# Manchester-Comparator_Module.net
KiCad netlist of a schematic drawn in Altium Designer
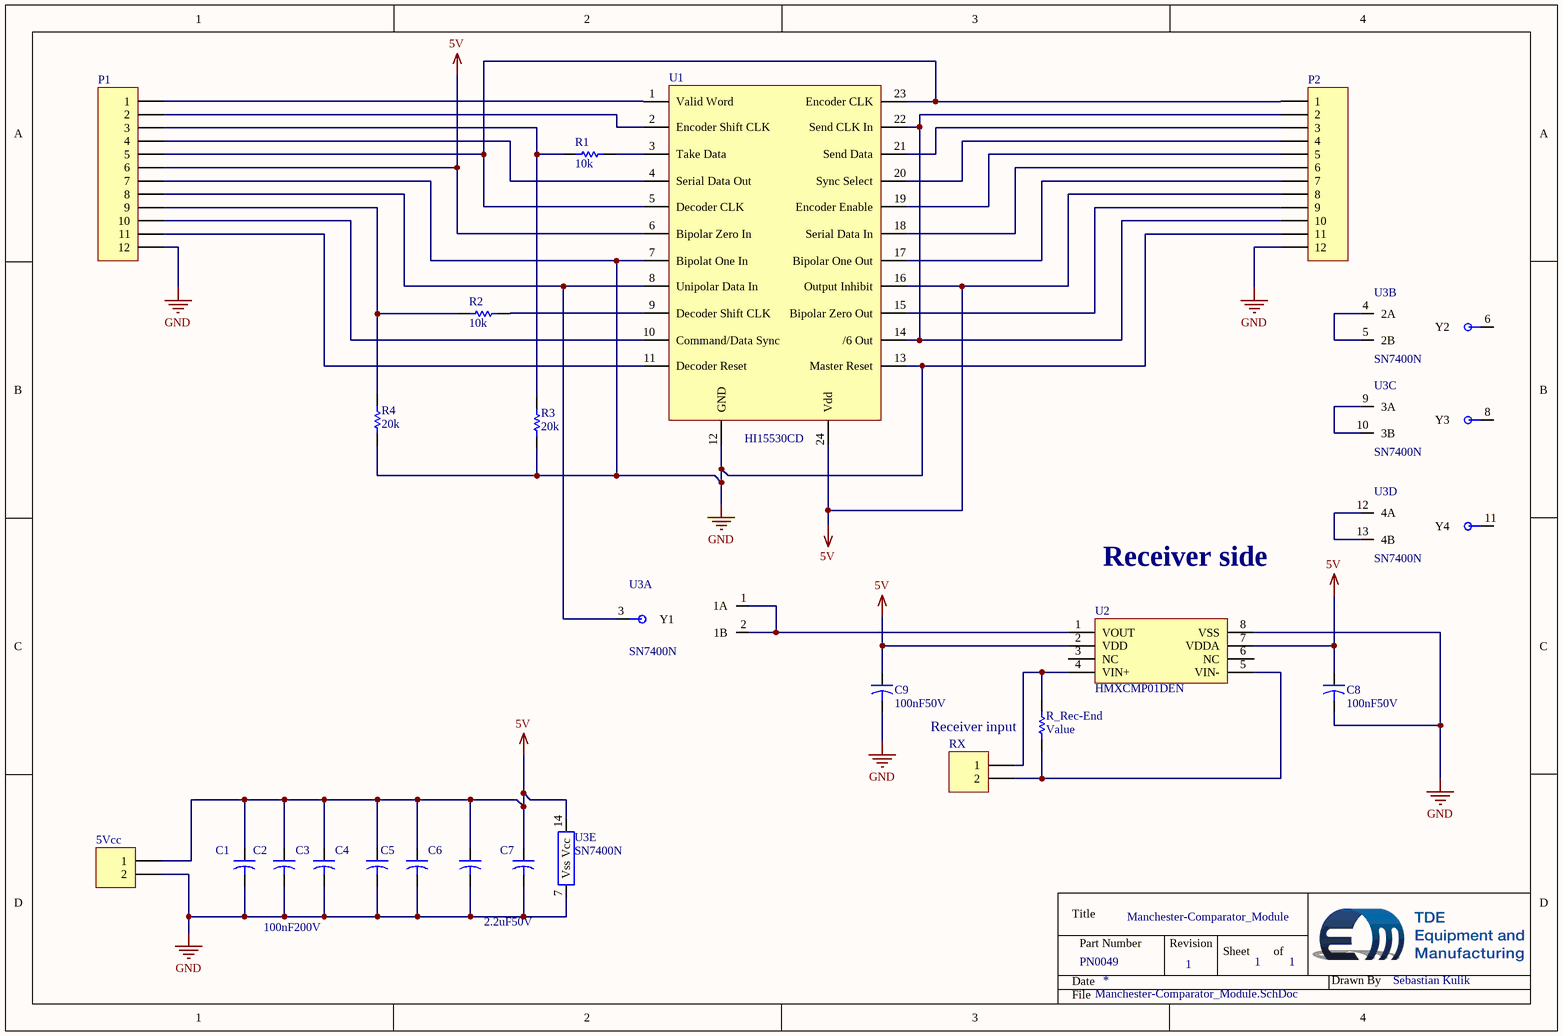
[diagram p0: Manchester-Comparator_Module.SchDoc]

(export (version "E")
  (design (tool "Eeschema 10.0.6"))
  (components
    (comp (ref "*") (value "Eye") (footprint "Eye") (libsource (lib "ICs") (part "Eye")))
    (comp (ref "**") (value "Eye") (footprint "Eye") (libsource (lib "ICs") (part "Eye")))
    (comp (ref "5Vcc")
      (value "PHOENIX_1715721")
      (footprint "Phoenix-2-5_08")
      (description "Phoenix, 2 pol, 5.08mm, 22A, 715721")
      (fields (field (name "MANUFACTURER") "Phoenix") (field (name "PUBLISHER") "Sebastian Kulik"))
      (libsource (lib "Connectors") (part "2Pol_1715721"))
    )
    (comp (ref "C1")
      (value "Capacitor-Dummy-THT")
      (footprint "Dummy-10mm")
      (fields (field (name "PUBLISHER") "Sebastian Kulik"))
      (libsource (lib "Capacitors") (part "Capacitor-Dummy-THT"))
    )
    (comp (ref "C2")
      (value "Capacitor-Dummy-THT")
      (footprint "Dummy-10mm")
      (fields (field (name "PUBLISHER") "Sebastian Kulik"))
      (libsource (lib "Capacitors") (part "Capacitor-Dummy-THT"))
    )
    (comp (ref "C3")
      (value "100nF200V")
      (footprint "Dummy-10mm")
      (description "Capacitor-Dummy-THT")
      (fields (field (name "PUBLISHER") "Sebastian Kulik"))
      (libsource (lib "Capacitors") (part "Capacitor-Dummy-THT"))
    )
    (comp (ref "C4")
      (value "Capacitor-Dummy-THT")
      (footprint "Dummy-10mm")
      (fields (field (name "PUBLISHER") "Sebastian Kulik"))
      (libsource (lib "Capacitors") (part "Capacitor-Dummy-THT"))
    )
    (comp (ref "C5")
      (value "Capacitor-Dummy-THT")
      (footprint "Dummy-10mm")
      (fields (field (name "PUBLISHER") "Sebastian Kulik"))
      (libsource (lib "Capacitors") (part "Capacitor-Dummy-THT"))
    )
    (comp (ref "C6")
      (value "Capacitor-Dummy-THT")
      (footprint "Dummy-10mm")
      (fields (field (name "PUBLISHER") "Sebastian Kulik"))
      (libsource (lib "Capacitors") (part "Capacitor-Dummy-THT"))
    )
    (comp (ref "C7")
      (value "2.2uF50V")
      (footprint "Dummy-10mm")
      (description "Capacitor-Dummy-THT")
      (fields (field (name "PUBLISHER") "Sebastian Kulik"))
      (libsource (lib "Capacitors") (part "Capacitor-Dummy-THT"))
    )
    (comp (ref "C8")
      (value "100nF50V")
      (footprint "KEMET-C052H")
      (description "High Temp C series, NP0, 10%, 50V")
      (fields
        (field (name "MANUFACTURER") "Kemet")
        (field (name "Comment") "100nF_50V_THT_HT")
        (field (name "PUBLISHER") "Sebastian Kulik")
      )
      (libsource (lib "Capacitors") (part "100nF_50V_THT_HT"))
    )
    (comp (ref "C9")
      (value "100nF50V")
      (footprint "KEMET-C052H")
      (description "High Temp C series, NP0, 10%, 50V")
      (fields
        (field (name "MANUFACTURER") "Kemet")
        (field (name "Comment") "100nF_50V_THT_HT")
        (field (name "PUBLISHER") "Sebastian Kulik")
      )
      (libsource (lib "Capacitors") (part "100nF_50V_THT_HT"))
    )
    (comp (ref "P1")
      (value "Plug_12_2.54")
      (footprint "HDR1X12_2.54")
      (description "Plug, 11-Pin")
      (fields (field (name "MANUFACTURER") "WE") (field (name "PUBLISHER") "Sebastian Kulik"))
      (libsource (lib "") (part "Plug_12_2.54_1"))
    )
    (comp (ref "P2")
      (value "Plug_12_2.54")
      (footprint "HDR1X12_2.54")
      (description "Plug, 11-Pin")
      (fields (field (name "MANUFACTURER") "WE") (field (name "PUBLISHER") "Sebastian Kulik"))
      (libsource (lib "Connectors") (part "Plug_12_2.54"))
    )
    (comp (ref "R1")
      (value "10k")
      (footprint "Dummy-10mm")
      (description "RN60 Series, 1%, 175°C")
      (fields
        (field (name "MANUFACTURER") "Vishay")
        (field (name "Comment") "10k_10mm-HT")
        (field (name "PUBLISHER") "Sebastian Kulik")
      )
      (libsource (lib "Resistors") (part "10k_10mm-HT"))
    )
    (comp (ref "R2")
      (value "10k")
      (footprint "Dummy-10mm")
      (description "RN60 Series, 1%, 175°C")
      (fields
        (field (name "MANUFACTURER") "Vishay")
        (field (name "Comment") "10k_10mm-HT")
        (field (name "PUBLISHER") "Sebastian Kulik")
      )
      (libsource (lib "Resistors") (part "10k_10mm-HT"))
    )
    (comp (ref "R3")
      (value "20k")
      (footprint "Dummy-10mm")
      (description "RN60 Series, 1%, 175°C")
      (fields
        (field (name "MANUFACTURER") "Vishay")
        (field (name "Comment") "20k_10mm-HT")
        (field (name "PUBLISHER") "Sebastian Kulik")
      )
      (libsource (lib "Resistors") (part "20k_10mm-HT"))
    )
    (comp (ref "R4")
      (value "20k")
      (footprint "Dummy-10mm")
      (description "RN60 Series, 1%, 175°C")
      (fields
        (field (name "MANUFACTURER") "Vishay")
        (field (name "Comment") "20k_10mm-HT")
        (field (name "PUBLISHER") "Sebastian Kulik")
      )
      (libsource (lib "Resistors") (part "20k_10mm-HT"))
    )
    (comp (ref "RX")
      (value "PHOENIX_1715721")
      (footprint "Phoenix-2-5_08")
      (description "Phoenix, 2 pol, 5.08mm, 22A, 715721")
      (fields (field (name "MANUFACTURER") "Phoenix") (field (name "PUBLISHER") "Sebastian Kulik"))
      (libsource (lib "Connectors") (part "2Pol_1715721"))
    )
    (comp (ref "R_Rec-End")
      (value "Value")
      (footprint "Dummy-10mm")
      (description "Resistor-Dummy-THT")
      (fields (field (name "PUBLISHER") "Sebastian Kulik"))
      (libsource (lib "Resistors") (part "Resistor-Dummy-THT"))
    )
    (comp (ref "U1")
      (value "HI15530CD")
      (footprint "DIP-24-Ceramic-HT")
      (description "Manchester Encoder / Decoder")
      (fields (field (name "MANUFACTURER") "HolTEc") (field (name "PUBLISHER") "Sebastian Kulik"))
      (libsource (lib "ICs") (part "HI15530CD"))
    )
    (comp (ref "U2")
      (value "HMXCMP01DEN")
      (footprint "Honeywell-SO8")
      (description "HiTemp Comparator")
      (fields (field (name "MANUFACTURER") "X-Rel") (field (name "PUBLISHER") "Sebastian Kulik"))
      (libsource (lib "ICs") (part "HMXCMP01DEN"))
    )
    (comp (ref "U3")
      (value "SN7400N")
      (footprint "DIP-14")
      (description "Quad NAND, TTL")
      (fields (field (name "MANUFACTURER") "TI") (field (name "PUBLISHER") "Sebastian Kulik"))
      (libsource (lib "") (part "SN7400N_1"))
    )
  )
  (nets
    (net (code "1") (name "5V") (class "Default")
      (node (ref "5Vcc") (pin "1") (pinfunction "1_1") (pintype "passive"))
      (node (ref "C1") (pin "1") (pinfunction "1_1") (pintype "passive"))
      (node (ref "C2") (pin "1") (pinfunction "1_1") (pintype "passive"))
      (node (ref "C3") (pin "1") (pinfunction "1_1") (pintype "passive"))
      (node (ref "C4") (pin "1") (pinfunction "1_1") (pintype "passive"))
      (node (ref "C5") (pin "1") (pinfunction "1_1") (pintype "passive"))
      (node (ref "C6") (pin "1") (pinfunction "1_1") (pintype "passive"))
      (node (ref "C7") (pin "1") (pinfunction "1_1") (pintype "passive"))
      (node (ref "C8") (pin "1") (pinfunction "1_1") (pintype "passive"))
      (node (ref "C9") (pin "1") (pinfunction "1_1") (pintype "passive"))
      (node (ref "P1") (pin "6") (pinfunction "6_6") (pintype "passive"))
      (node (ref "P2") (pin "8") (pinfunction "8_8") (pintype "passive"))
      (node (ref "U1") (pin "16") (pinfunction "Output_Inhibit_16") (pintype "passive"))
      (node (ref "U1") (pin "24") (pinfunction "Vdd_24") (pintype "passive"))
      (node (ref "U1") (pin "6") (pinfunction "Bipolar_Zero_In_6") (pintype "passive"))
      (node (ref "U2") (pin "2") (pinfunction "VDD_2") (pintype "passive"))
      (node (ref "U2") (pin "7") (pinfunction "VDDA_7") (pintype "passive"))
      (node (ref "U3") (pin "14") (pinfunction "Vcc_14") (pintype "passive"))
    )
    (net (code "2") (name "GND") (class "Default")
      (node (ref "5Vcc") (pin "2") (pinfunction "2_2") (pintype "passive"))
      (node (ref "C1") (pin "2") (pinfunction "2_2") (pintype "passive"))
      (node (ref "C2") (pin "2") (pinfunction "2_2") (pintype "passive"))
      (node (ref "C3") (pin "2") (pinfunction "2_2") (pintype "passive"))
      (node (ref "C4") (pin "2") (pinfunction "2_2") (pintype "passive"))
      (node (ref "C5") (pin "2") (pinfunction "2_2") (pintype "passive"))
      (node (ref "C6") (pin "2") (pinfunction "2_2") (pintype "passive"))
      (node (ref "C7") (pin "2") (pinfunction "2_2") (pintype "passive"))
      (node (ref "C8") (pin "2") (pinfunction "2_2") (pintype "passive"))
      (node (ref "C9") (pin "2") (pinfunction "2_2") (pintype "passive"))
      (node (ref "P1") (pin "12") (pinfunction "12_12") (pintype "passive"))
      (node (ref "P1") (pin "7") (pinfunction "7_7") (pintype "passive"))
      (node (ref "P2") (pin "11") (pinfunction "11_11") (pintype "passive"))
      (node (ref "P2") (pin "12") (pinfunction "12_12") (pintype "passive"))
      (node (ref "R3") (pin "1") (pinfunction "1_1") (pintype "passive"))
      (node (ref "R4") (pin "1") (pinfunction "1_1") (pintype "passive"))
      (node (ref "U1") (pin "12") (pinfunction "GND_12") (pintype "power_in"))
      (node (ref "U1") (pin "13") (pinfunction "Master_Reset_13") (pintype "passive"))
      (node (ref "U1") (pin "7") (pinfunction "Bipolat_One_In_7") (pintype "passive"))
      (node (ref "U2") (pin "8") (pinfunction "VSS_8") (pintype "passive"))
      (node (ref "U3") (pin "7") (pinfunction "Vss_7") (pintype "passive"))
    )
    (net (code "3") (name "Net-(P1-Pad3)") (class "Default")
      (node (ref "P1") (pin "3") (pinfunction "3_3") (pintype "passive"))
      (node (ref "R1") (pin "2") (pinfunction "2_2") (pintype "passive"))
      (node (ref "R3") (pin "2") (pinfunction "2_2") (pintype "passive"))
    )
    (net (code "4") (name "Net-(P1-Pad9)") (class "Default")
      (node (ref "P1") (pin "9") (pinfunction "9_9") (pintype "passive"))
      (node (ref "R2") (pin "2") (pinfunction "2_2") (pintype "passive"))
      (node (ref "R4") (pin "2") (pinfunction "2_2") (pintype "passive"))
    )
    (net (code "5") (name "Net-(U1-Bipolar_One_Out)") (class "Default")
      (node (ref "P2") (pin "7") (pinfunction "7_7") (pintype "passive"))
      (node (ref "U1") (pin "17") (pinfunction "Bipolar_One_Out_17") (pintype "passive"))
    )
    (net (code "6") (name "Net-(U1-Bipolar_Zero_Out)") (class "Default")
      (node (ref "P2") (pin "9") (pinfunction "9_9") (pintype "passive"))
      (node (ref "U1") (pin "15") (pinfunction "Bipolar_Zero_Out_15") (pintype "power_in"))
    )
    (net (code "7") (name "Net-(U1-Command{slash}Data_Sync)") (class "Default")
      (node (ref "P1") (pin "10") (pinfunction "10_10") (pintype "passive"))
      (node (ref "U1") (pin "10") (pinfunction "Command/Data_Sync_10") (pintype "power_in"))
    )
    (net (code "8") (name "Net-(U1-Decoder_CLK)") (class "Default")
      (node (ref "P1") (pin "5") (pinfunction "5_5") (pintype "passive"))
      (node (ref "P2") (pin "1") (pinfunction "1_1") (pintype "passive"))
      (node (ref "U1") (pin "23") (pinfunction "Encoder_CLK_23") (pintype "passive"))
      (node (ref "U1") (pin "5") (pinfunction "Decoder_CLK_5") (pintype "passive"))
    )
    (net (code "9") (name "Net-(U1-Decoder_Reset)") (class "Default")
      (node (ref "P1") (pin "11") (pinfunction "11_11") (pintype "passive"))
      (node (ref "U1") (pin "11") (pinfunction "Decoder_Reset_11") (pintype "power_in"))
    )
    (net (code "10") (name "Net-(U1-Decoder_Shift_CLK)") (class "Default")
      (node (ref "R2") (pin "1") (pinfunction "1_1") (pintype "passive"))
      (node (ref "U1") (pin "9") (pinfunction "Decoder_Shift_CLK_9") (pintype "power_in"))
    )
    (net (code "11") (name "Net-(U1-Encoder_Enable)") (class "Default")
      (node (ref "P2") (pin "5") (pinfunction "5_5") (pintype "passive"))
      (node (ref "U1") (pin "19") (pinfunction "Encoder_Enable_19") (pintype "passive"))
    )
    (net (code "12") (name "Net-(U1-Encoder_Shift_CLK)") (class "Default")
      (node (ref "P1") (pin "2") (pinfunction "2_2") (pintype "passive"))
      (node (ref "U1") (pin "2") (pinfunction "Encoder_Shift_CLK_2") (pintype "passive"))
    )
    (net (code "13") (name "Net-(U1-Send_CLK_In)") (class "Default")
      (node (ref "P2") (pin "10") (pinfunction "10_10") (pintype "passive"))
      (node (ref "P2") (pin "2") (pinfunction "2_2") (pintype "passive"))
      (node (ref "U1") (pin "14") (pinfunction "/6_Out_14") (pintype "passive"))
      (node (ref "U1") (pin "22") (pinfunction "Send_CLK_In_22") (pintype "passive"))
    )
    (net (code "14") (name "Net-(U1-Send_Data)") (class "Default")
      (node (ref "P2") (pin "3") (pinfunction "3_3") (pintype "passive"))
      (node (ref "U1") (pin "21") (pinfunction "Send_Data_21") (pintype "passive"))
    )
    (net (code "15") (name "Net-(U1-Serial_Data_In)") (class "Default")
      (node (ref "P2") (pin "6") (pinfunction "6_6") (pintype "passive"))
      (node (ref "U1") (pin "18") (pinfunction "Serial_Data_In_18") (pintype "passive"))
    )
    (net (code "16") (name "Net-(U1-Serial_Data_Out)") (class "Default")
      (node (ref "P1") (pin "4") (pinfunction "4_4") (pintype "passive"))
      (node (ref "U1") (pin "4") (pinfunction "Serial_Data_Out_4") (pintype "passive"))
    )
    (net (code "17") (name "Net-(U1-Sync_Select)") (class "Default")
      (node (ref "P2") (pin "4") (pinfunction "4_4") (pintype "passive"))
      (node (ref "U1") (pin "20") (pinfunction "Sync_Select_20") (pintype "passive"))
    )
    (net (code "18") (name "Net-(U1-Take_Data)") (class "Default")
      (node (ref "R1") (pin "1") (pinfunction "1_1") (pintype "passive"))
      (node (ref "U1") (pin "3") (pinfunction "Take_Data_3") (pintype "passive"))
    )
    (net (code "19") (name "Net-(U1-Unipolar_Data_In)") (class "Default")
      (node (ref "P1") (pin "8") (pinfunction "8_8") (pintype "passive"))
      (node (ref "U1") (pin "8") (pinfunction "Unipolar_Data_In_8") (pintype "power_in"))
      (node (ref "U3") (pin "3") (pinfunction "Y1_3") (pintype "passive"))
    )
    (net (code "20") (name "Net-(U1-Valid_Word)") (class "Default")
      (node (ref "P1") (pin "1") (pinfunction "1_1") (pintype "passive"))
      (node (ref "U1") (pin "1") (pinfunction "Valid_Word_1") (pintype "passive"))
    )
    (net (code "21") (name "Net-(U2-VIN+)") (class "Default")
      (node (ref "RX") (pin "1") (pinfunction "1_1") (pintype "passive"))
      (node (ref "R_Rec-End") (pin "2") (pinfunction "2_2") (pintype "passive"))
      (node (ref "U2") (pin "4") (pinfunction "VIN+_4") (pintype "passive"))
    )
    (net (code "22") (name "Net-(U2-VIN-)") (class "Default")
      (node (ref "RX") (pin "2") (pinfunction "2_2") (pintype "passive"))
      (node (ref "R_Rec-End") (pin "1") (pinfunction "1_1") (pintype "passive"))
      (node (ref "U2") (pin "5") (pinfunction "VIN-_5") (pintype "passive"))
    )
    (net (code "23") (name "Net-(U2-VOUT)") (class "Default")
      (node (ref "U2") (pin "1") (pinfunction "VOUT_1") (pintype "passive"))
      (node (ref "U3") (pin "1") (pinfunction "1A_1") (pintype "passive"))
      (node (ref "U3") (pin "2") (pinfunction "1B_2") (pintype "passive"))
    )
    (net (code "24") (name "Net-(U3B-2A)") (class "Default")
      (node (ref "U3") (pin "4") (pinfunction "2A_4") (pintype "passive"))
      (node (ref "U3") (pin "5") (pinfunction "2B_5") (pintype "passive"))
    )
    (net (code "25") (name "Net-(U3C-3A)") (class "Default")
      (node (ref "U3") (pin "10") (pinfunction "3B_10") (pintype "passive"))
      (node (ref "U3") (pin "9") (pinfunction "3A_9") (pintype "passive"))
    )
    (net (code "26") (name "Net-(U3D-4A)") (class "Default")
      (node (ref "U3") (pin "12") (pinfunction "4A_12") (pintype "passive"))
      (node (ref "U3") (pin "13") (pinfunction "4B_13") (pintype "passive"))
    )
    (net (code "27") (name "unconnected-(U2-NC-Pad3)") (class "Default")
      (node (ref "U2") (pin "3") (pinfunction "NC_3") (pintype "passive"))
    )
    (net (code "28") (name "unconnected-(U2-NC-Pad6)") (class "Default")
      (node (ref "U2") (pin "6") (pinfunction "NC_6") (pintype "passive"))
    )
    (net (code "29") (name "unconnected-(U3B-Y2-Pad6)") (class "Default")
      (node (ref "U3") (pin "6") (pinfunction "Y2_6") (pintype "passive"))
    )
    (net (code "30") (name "unconnected-(U3C-Y3-Pad8)") (class "Default")
      (node (ref "U3") (pin "8") (pinfunction "Y3_8") (pintype "passive"))
    )
    (net (code "31") (name "unconnected-(U3D-Y4-Pad11)") (class "Default")
      (node (ref "U3") (pin "11") (pinfunction "Y4_11") (pintype "passive"))
    )
  )
)
